# Analog_Voltmeter.net
KiCad netlist of a schematic drawn in Altium Designer
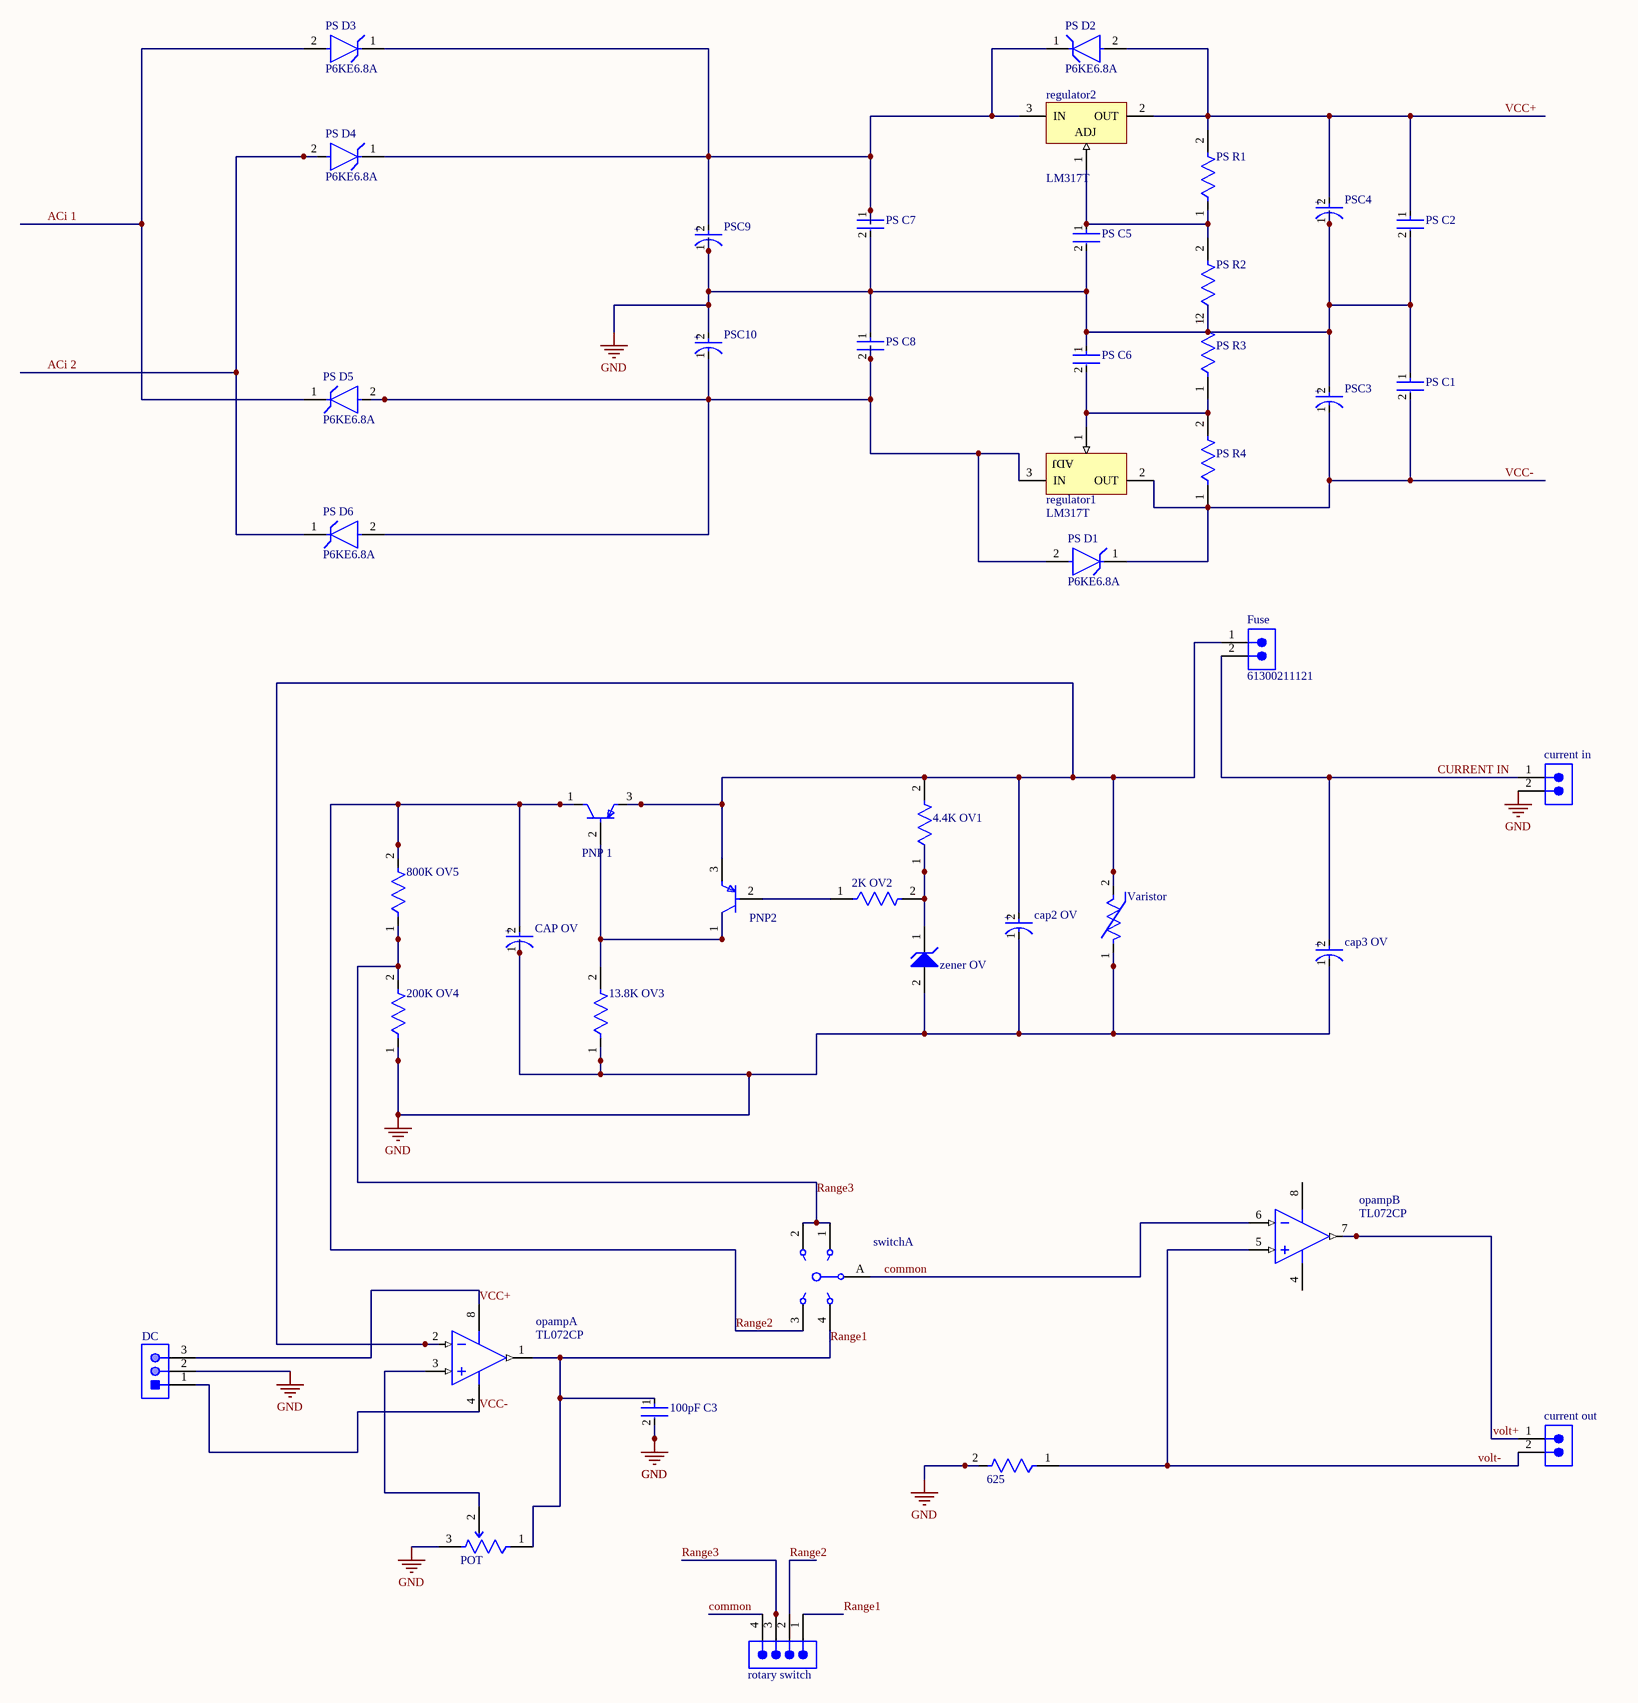
[diagram p0: Analog Voltmeter.SchDoc]

(export (version "E")
  (design (tool "Eeschema 10.0.6"))
  (components
    (comp (ref "2K OV2")
      (value "MRS25000C1002FCT00")
      (footprint "FP-MRS25-MFG")
      (fields (field (name "TOLERANCE") "1%"))
      (libsource (lib "Altium Content Vault") (part "1029c3af85768c4190bb7ad29bc67b5"))
    )
    (comp (ref "4.4K OV1")
      (value "MRS25000C1002FCT00")
      (footprint "FP-MRS25-MFG")
      (fields (field (name "TOLERANCE") "1%"))
      (libsource (lib "Altium Content Vault") (part "1029c3af85768c4190bb7ad29bc67b5"))
    )
    (comp (ref "13.8K OV3")
      (value "MRS25000C1002FCT00")
      (footprint "FP-MRS25-MFG")
      (fields (field (name "TOLERANCE") "1%"))
      (libsource (lib "Altium Content Vault") (part "1029c3af85768c4190bb7ad29bc67b5"))
    )
    (comp (ref "100pF C3")
      (value "K104K15X7RF5TH5")
      (footprint "FP-K15H5-MFG")
      (description "CAP CER 0.1UF 50V X7R RADIAL")
      (fields (field (name "TOLERANCE") "10%") (field (name "VOLTAGE") "50V"))
      (libsource (lib "Altium Content Vault") (part "02cd4be3c70576c341d710602a673aa"))
    )
    (comp (ref "200K OV4")
      (value "MRS25000C1002FCT00")
      (footprint "FP-MRS25-MFG")
      (fields (field (name "TOLERANCE") "1%"))
      (libsource (lib "Altium Content Vault") (part "1029c3af85768c4190bb7ad29bc67b5"))
    )
    (comp (ref "625")
      (value "MRS25000C1002FCT00")
      (footprint "FP-MRS25-MFG")
      (fields (field (name "TOLERANCE") "1%"))
      (libsource (lib "Altium Content Vault") (part "1029c3af85768c4190bb7ad29bc67b5"))
    )
    (comp (ref "800K OV5")
      (value "MRS25000C1002FCT00")
      (footprint "FP-MRS25-MFG")
      (fields (field (name "TOLERANCE") "1%"))
      (libsource (lib "Altium Content Vault") (part "1029c3af85768c4190bb7ad29bc67b5"))
    )
    (comp (ref "CAP OV")
      (value "ESL107M050AGMAA")
      (footprint "FP-ESLGM-MFG")
      (description "CAP ALUM 100UF 20% 50V THRU HOLE")
      (fields
        (field (name "TOLERANCE") "20%")
        (field (name "OCTOPART") "https://octopart.com/esl107m050agmaa-kemet-84758890")
      )
      (libsource (lib "Altium Content Vault") (part "a00bbbee19879c290e62620ae7e47b1"))
    )
    (comp (ref "cap2 OV")
      (value "ESL107M050AGMAA")
      (footprint "FP-ESLGM-MFG")
      (description "CAP ALUM 100UF 20% 50V THRU HOLE")
      (fields
        (field (name "TOLERANCE") "20%")
        (field (name "OCTOPART") "https://octopart.com/esl107m050agmaa-kemet-84758890")
      )
      (libsource (lib "Altium Content Vault") (part "a00bbbee19879c290e62620ae7e47b1"))
    )
    (comp (ref "cap3 OV")
      (value "ESL107M050AGMAA")
      (footprint "FP-ESLGM-MFG")
      (description "CAP ALUM 100UF 20% 50V THRU HOLE")
      (fields
        (field (name "TOLERANCE") "20%")
        (field (name "OCTOPART") "https://octopart.com/esl107m050agmaa-kemet-84758890")
      )
      (libsource (lib "Altium Content Vault") (part "a00bbbee19879c290e62620ae7e47b1"))
    )
    (comp (ref "current in")
      (value "61300211121")
      (footprint "61300211121")
      (libsource (lib "Altium Content Vault") (part "Header_Male_1R_02P"))
    )
    (comp (ref "current out")
      (value "61300211121")
      (footprint "61300211121")
      (libsource (lib "Altium Content Vault") (part "Header_Male_1R_02P"))
    )
    (comp (ref "DC")
      (value "22-28-4033")
      (footprint "MOLX-22-28-4033_V")
      (description "Male Header, Pitch 2.54 mm, 1 x 3 Position, Height 8.38 mm, Tail Length 3.18 mm, RoHS, Bulk")
      (fields (field (name "MANUFACTURER") "Molex"))
      (libsource (lib "Altium Content Vault") (part "CN-1P-M-R3"))
    )
    (comp (ref "Fuse")
      (value "61300211121")
      (footprint "61300211121")
      (libsource (lib "Altium Content Vault") (part "Header_Male_1R_02P"))
    )
    (comp (ref "opamp")
      (value "TL072CP")
      (footprint "P0008A")
      (fields (field (name "MANUFACTURER") "Texas Instruments"))
      (libsource (lib "Altium Content Vault") (part "TI-AMP-D6-2-8_D"))
    )
    (comp (ref "PNP 1")
      (value "BC558BTA")
      (footprint "FP-135AR-MFG")
      (description "BC558BTA Small Signal Bipolar Transistor, 0.1A I(C), 30V V(BR)CEO, 1-Element, PNP, Silicon, TO-92")
      (libsource (lib "Altium Content Vault") (part "9e2844d3eb996af6824d2c99fe21afc"))
    )
    (comp (ref "PNP2")
      (value "BC558BTA")
      (footprint "FP-135AR-MFG")
      (description "BC558BTA Small Signal Bipolar Transistor, 0.1A I(C), 30V V(BR)CEO, 1-Element, PNP, Silicon, TO-92")
      (libsource (lib "Altium Content Vault") (part "9e2844d3eb996af6824d2c99fe21afc"))
    )
    (comp (ref "POT")
      (value "3362P-1-503TLF")
      (footprint "FP-3362P-1-503TLF-MFG")
      (description "TRIMMER 50K OHM 0.5W PC PIN TOP")
      (fields (field (name "TOLERANCE") "10%"))
      (libsource (lib "Altium Content Vault") (part "2dcfd2547301a7d3209a5e99acfd772"))
    )
    (comp (ref "PS C1")
      (value "K104K15X7RF5TH5")
      (footprint "FP-K15H5-MFG")
      (description "CAP CER 0.1UF 50V X7R RADIAL")
      (fields (field (name "TOLERANCE") "10%") (field (name "VOLTAGE") "50V"))
      (libsource (lib "Altium Content Vault") (part "02cd4be3c70576c341d710602a673aa"))
    )
    (comp (ref "PS C2")
      (value "K104K15X7RF5TH5")
      (footprint "FP-K15H5-MFG")
      (description "CAP CER 0.1UF 50V X7R RADIAL")
      (fields (field (name "TOLERANCE") "10%") (field (name "VOLTAGE") "50V"))
      (libsource (lib "Altium Content Vault") (part "02cd4be3c70576c341d710602a673aa"))
    )
    (comp (ref "PS C5")
      (value "K104K15X7RF5TH5")
      (footprint "FP-K15H5-MFG")
      (description "CAP CER 0.1UF 50V X7R RADIAL")
      (fields (field (name "TOLERANCE") "10%") (field (name "VOLTAGE") "50V"))
      (libsource (lib "Altium Content Vault") (part "02cd4be3c70576c341d710602a673aa"))
    )
    (comp (ref "PS C6")
      (value "K104K15X7RF5TH5")
      (footprint "FP-K15H5-MFG")
      (description "CAP CER 0.1UF 50V X7R RADIAL")
      (fields (field (name "TOLERANCE") "10%") (field (name "VOLTAGE") "50V"))
      (libsource (lib "Altium Content Vault") (part "02cd4be3c70576c341d710602a673aa"))
    )
    (comp (ref "PS C7")
      (value "K104K15X7RF5TH5")
      (footprint "FP-K15H5-MFG")
      (description "CAP CER 0.1UF 50V X7R RADIAL")
      (fields (field (name "TOLERANCE") "10%") (field (name "VOLTAGE") "50V"))
      (libsource (lib "Altium Content Vault") (part "02cd4be3c70576c341d710602a673aa"))
    )
    (comp (ref "PS C8")
      (value "K104K15X7RF5TH5")
      (footprint "FP-K15H5-MFG")
      (description "CAP CER 0.1UF 50V X7R RADIAL")
      (fields (field (name "TOLERANCE") "10%") (field (name "VOLTAGE") "50V"))
      (libsource (lib "Altium Content Vault") (part "02cd4be3c70576c341d710602a673aa"))
    )
    (comp (ref "PS D1")
      (value "P6KE6.8A")
      (footprint "FP-P6KE-MFG")
      (description "TVS DIODE 5.8V 10.5V DO204AC")
      (fields
        (field (name "MANUFACTURER") "Littelfuse Inc")
        (field (name "OCTOPART") "https://octopart.com/p6ke6.8a-littelfuse-20808")
      )
      (libsource (lib "Altium Content Vault") (part "f813f71cba58e380607f5dd3caf9714"))
    )
    (comp (ref "PS D2")
      (value "P6KE6.8A")
      (footprint "FP-P6KE-MFG")
      (description "TVS DIODE 5.8V 10.5V DO204AC")
      (fields
        (field (name "MANUFACTURER") "Littelfuse Inc")
        (field (name "OCTOPART") "https://octopart.com/p6ke6.8a-littelfuse-20808")
      )
      (libsource (lib "Altium Content Vault") (part "f813f71cba58e380607f5dd3caf9714"))
    )
    (comp (ref "PS D3")
      (value "P6KE6.8A")
      (footprint "FP-P6KE-MFG")
      (description "TVS DIODE 5.8V 10.5V DO204AC")
      (fields
        (field (name "MANUFACTURER") "Littelfuse Inc")
        (field (name "OCTOPART") "https://octopart.com/p6ke6.8a-littelfuse-20808")
      )
      (libsource (lib "Altium Content Vault") (part "f813f71cba58e380607f5dd3caf9714"))
    )
    (comp (ref "PS D4")
      (value "P6KE6.8A")
      (footprint "FP-P6KE-MFG")
      (description "TVS DIODE 5.8V 10.5V DO204AC")
      (fields
        (field (name "MANUFACTURER") "Littelfuse Inc")
        (field (name "OCTOPART") "https://octopart.com/p6ke6.8a-littelfuse-20808")
      )
      (libsource (lib "Altium Content Vault") (part "f813f71cba58e380607f5dd3caf9714"))
    )
    (comp (ref "PS D5")
      (value "P6KE6.8A")
      (footprint "FP-P6KE-MFG")
      (description "TVS DIODE 5.8V 10.5V DO204AC")
      (fields
        (field (name "MANUFACTURER") "Littelfuse Inc")
        (field (name "OCTOPART") "https://octopart.com/p6ke6.8a-littelfuse-20808")
      )
      (libsource (lib "Altium Content Vault") (part "f813f71cba58e380607f5dd3caf9714"))
    )
    (comp (ref "PS D6")
      (value "P6KE6.8A")
      (footprint "FP-P6KE-MFG")
      (description "TVS DIODE 5.8V 10.5V DO204AC")
      (fields
        (field (name "MANUFACTURER") "Littelfuse Inc")
        (field (name "OCTOPART") "https://octopart.com/p6ke6.8a-littelfuse-20808")
      )
      (libsource (lib "Altium Content Vault") (part "f813f71cba58e380607f5dd3caf9714"))
    )
    (comp (ref "PS R1")
      (value "MRS25000C1002FCT00")
      (footprint "FP-MRS25-MFG")
      (fields (field (name "TOLERANCE") "1%"))
      (libsource (lib "Altium Content Vault") (part "1029c3af85768c4190bb7ad29bc67b5"))
    )
    (comp (ref "PS R2")
      (value "MRS25000C1002FCT00")
      (footprint "FP-MRS25-MFG")
      (fields (field (name "TOLERANCE") "1%"))
      (libsource (lib "Altium Content Vault") (part "1029c3af85768c4190bb7ad29bc67b5"))
    )
    (comp (ref "PS R3")
      (value "MRS25000C1002FCT00")
      (footprint "FP-MRS25-MFG")
      (fields (field (name "TOLERANCE") "1%"))
      (libsource (lib "Altium Content Vault") (part "1029c3af85768c4190bb7ad29bc67b5"))
    )
    (comp (ref "PS R4")
      (value "MRS25000C1002FCT00")
      (footprint "FP-MRS25-MFG")
      (fields (field (name "TOLERANCE") "1%"))
      (libsource (lib "Altium Content Vault") (part "1029c3af85768c4190bb7ad29bc67b5"))
    )
    (comp (ref "PSC3")
      (value "ESL107M050AGMAA")
      (footprint "FP-ESLGM-MFG")
      (description "CAP ALUM 100UF 20% 50V THRU HOLE")
      (fields
        (field (name "TOLERANCE") "20%")
        (field (name "OCTOPART") "https://octopart.com/esl107m050agmaa-kemet-84758890")
      )
      (libsource (lib "Altium Content Vault") (part "a00bbbee19879c290e62620ae7e47b1"))
    )
    (comp (ref "PSC4")
      (value "ESL107M050AGMAA")
      (footprint "FP-ESLGM-MFG")
      (description "CAP ALUM 100UF 20% 50V THRU HOLE")
      (fields
        (field (name "TOLERANCE") "20%")
        (field (name "OCTOPART") "https://octopart.com/esl107m050agmaa-kemet-84758890")
      )
      (libsource (lib "Altium Content Vault") (part "a00bbbee19879c290e62620ae7e47b1"))
    )
    (comp (ref "PSC9")
      (value "ESL107M050AGMAA")
      (footprint "FP-ESLGM-MFG")
      (description "CAP ALUM 100UF 20% 50V THRU HOLE")
      (fields
        (field (name "TOLERANCE") "20%")
        (field (name "OCTOPART") "https://octopart.com/esl107m050agmaa-kemet-84758890")
      )
      (libsource (lib "Altium Content Vault") (part "a00bbbee19879c290e62620ae7e47b1"))
    )
    (comp (ref "PSC10")
      (value "ESL107M050AGMAA")
      (footprint "FP-ESLGM-MFG")
      (description "CAP ALUM 100UF 20% 50V THRU HOLE")
      (fields
        (field (name "TOLERANCE") "20%")
        (field (name "OCTOPART") "https://octopart.com/esl107m050agmaa-kemet-84758890")
      )
      (libsource (lib "Altium Content Vault") (part "a00bbbee19879c290e62620ae7e47b1"))
    )
    (comp (ref "regulator1")
      (value "LM317T")
      (footprint "TO-220")
      (description "1.5A, 1.2V to 37V Adjustable Voltage Regulator, 3-Pin TO-220")
      (libsource (lib "Altium Content Vault") (part "PM-REG-117-SIL3"))
    )
    (comp (ref "regulator2")
      (value "LM317T")
      (footprint "TO-220")
      (description "1.5A, 1.2V to 37V Adjustable Voltage Regulator, 3-Pin TO-220")
      (libsource (lib "") (part "PM-REG-117-SIL3_1"))
    )
    (comp (ref "rotary switch")
      (value "61300411121")
      (footprint "61300411121")
      (libsource (lib "Altium Content Vault") (part "Header_Male_1R_04P"))
    )
    (comp (ref "switch")
      (value "A30415RNCQ")
      (footprint "CKCP-A30415RNCQ-15_V")
      (description "A Series Rotary Switch, 3 Poles, 4 Positions, 30 deg Angle of Throw, -30 to 85 degC, RoHS")
      (fields (field (name "MANUFACTURER") "C&K Components"))
      (libsource (lib "Altium Content Vault") (part "CKCP-SW_3P4T-15"))
    )
    (comp (ref "Varistor")
      (value "MOV-10D201KTR")
      (footprint "FP-MOV-10D201KTR-MFG")
      (description "VARISTOR 200V 2.5KA DISC 10MM")
      (fields
        (field (name "MANUFACTURER") "Bourns Inc.")
        (field (name "OCTOPART") "https://octopart.com/mov-10d201ktr-bourns-19184757")
      )
      (libsource (lib "Altium Content Vault") (part "78a88060d5b7b043d6e48adc4284376"))
    )
    (comp (ref "zener OV")
      (value "1N5347BRLG")
      (footprint "ONSC-SURMETIC40-2-017AA-01")
      (description "5 W Zener Voltage Regulator, 2-Pin Surmetic(TM) 40, Pb-Free, Tape and Reel")
      (fields (field (name "MANUFACTURER") "On Semiconductor"))
      (libsource (lib "Altium Content Vault") (part "ONSC-K1A2-2"))
    )
  )
  (nets
    (net (code "2") (name "/ACi 1") (class "Default")
      (node (ref "PS D3") (pin "2") (pinfunction "A_2") (pintype "passive"))
      (node (ref "PS D5") (pin "1") (pinfunction "C_1") (pintype "passive"))
    )
    (net (code "3") (name "/ACi 2") (class "Default")
      (node (ref "PS D4") (pin "2") (pinfunction "A_2") (pintype "passive"))
      (node (ref "PS D6") (pin "1") (pinfunction "C_1") (pintype "passive"))
    )
    (net (code "4") (name "/CURRENT IN") (class "Default")
      (node (ref "Fuse") (pin "2") (pinfunction "2_2") (pintype "passive"))
      (node (ref "cap3 OV") (pin "2") (pinfunction "A_2") (pintype "passive"))
      (node (ref "current in") (pin "1") (pinfunction "1_1") (pintype "passive"))
    )
    (net (code "5") (name "/Range1") (class "Default")
      (node (ref "100pF C3") (pin "1") (pinfunction "1_1") (pintype "passive"))
      (node (ref "POT") (pin "1") (pinfunction "CCW_1") (pintype "passive"))
      (node (ref "opamp") (pin "1") (pinfunction "OUT1_1") (pintype "output"))
      (node (ref "rotary switch") (pin "1") (pinfunction "1_1") (pintype "passive"))
      (node (ref "switch") (pin "4") (pinfunction "4_4") (pintype "passive"))
    )
    (net (code "6") (name "/Range2") (class "Default")
      (node (ref "800K OV5") (pin "2") (pinfunction "2_2") (pintype "passive"))
      (node (ref "CAP OV") (pin "2") (pinfunction "A_2") (pintype "passive"))
      (node (ref "PNP 1") (pin "1") (pinfunction "C_1") (pintype "passive"))
      (node (ref "rotary switch") (pin "2") (pinfunction "2_2") (pintype "passive"))
      (node (ref "switch") (pin "3") (pinfunction "3_3") (pintype "passive"))
    )
    (net (code "7") (name "/Range3") (class "Default")
      (node (ref "200K OV4") (pin "2") (pinfunction "2_2") (pintype "passive"))
      (node (ref "800K OV5") (pin "1") (pinfunction "1_1") (pintype "passive"))
      (node (ref "rotary switch") (pin "3") (pinfunction "3_3") (pintype "passive"))
      (node (ref "switch") (pin "1") (pinfunction "1_1") (pintype "passive"))
      (node (ref "switch") (pin "2") (pinfunction "2_2") (pintype "passive"))
    )
    (net (code "8") (name "/VCC+") (class "Default")
      (node (ref "DC") (pin "3") (pinfunction "3_3") (pintype "passive"))
      (node (ref "PS C2") (pin "1") (pinfunction "1_1") (pintype "passive"))
      (node (ref "PS D2") (pin "2") (pinfunction "A_2") (pintype "passive"))
      (node (ref "PS R1") (pin "2") (pinfunction "2_2") (pintype "passive"))
      (node (ref "PSC4") (pin "2") (pinfunction "A_2") (pintype "passive"))
      (node (ref "opamp") (pin "8") (pinfunction "VCC+_8") (pintype "power_in"))
      (node (ref "regulator2") (pin "2") (pinfunction "OUT_2") (pintype "power_in"))
    )
    (net (code "9") (name "/VCC-") (class "Default")
      (node (ref "DC") (pin "1") (pinfunction "1_1") (pintype "passive"))
      (node (ref "PS C1") (pin "2") (pinfunction "2_2") (pintype "passive"))
      (node (ref "PS D1") (pin "1") (pinfunction "C_1") (pintype "passive"))
      (node (ref "PS R4") (pin "1") (pinfunction "1_1") (pintype "passive"))
      (node (ref "PSC3") (pin "1") (pinfunction "C_1") (pintype "passive"))
      (node (ref "opamp") (pin "4") (pinfunction "VCC-_4") (pintype "power_in"))
      (node (ref "regulator1") (pin "2") (pinfunction "OUT_2") (pintype "power_in"))
    )
    (net (code "10") (name "/common") (class "Default")
      (node (ref "opamp") (pin "6") (pinfunction "IN2-_6") (pintype "input"))
      (node (ref "rotary switch") (pin "4") (pinfunction "4_4") (pintype "passive"))
      (node (ref "switch") (pin "A") (pinfunction "A_A") (pintype "passive"))
    )
    (net (code "11") (name "/volt+") (class "Default")
      (node (ref "current out") (pin "1") (pinfunction "1_1") (pintype "passive"))
      (node (ref "opamp") (pin "7") (pinfunction "OUT2_7") (pintype "output"))
    )
    (net (code "12") (name "/volt-") (class "Default")
      (node (ref "625") (pin "1") (pinfunction "1_1") (pintype "passive"))
      (node (ref "current out") (pin "2") (pinfunction "2_2") (pintype "passive"))
      (node (ref "opamp") (pin "5") (pinfunction "IN2+_5") (pintype "input"))
    )
    (net (code "13") (name "GND") (class "Default")
      (node (ref "100pF C3") (pin "2") (pinfunction "2_2") (pintype "passive"))
      (node (ref "13.8K OV3") (pin "1") (pinfunction "1_1") (pintype "passive"))
      (node (ref "200K OV4") (pin "1") (pinfunction "1_1") (pintype "passive"))
      (node (ref "625") (pin "2") (pinfunction "2_2") (pintype "passive"))
      (node (ref "CAP OV") (pin "1") (pinfunction "C_1") (pintype "passive"))
      (node (ref "DC") (pin "2") (pinfunction "2_2") (pintype "passive"))
      (node (ref "POT") (pin "3") (pinfunction "CW_3") (pintype "passive"))
      (node (ref "PS C1") (pin "1") (pinfunction "1_1") (pintype "passive"))
      (node (ref "PS C2") (pin "2") (pinfunction "2_2") (pintype "passive"))
      (node (ref "PS C5") (pin "2") (pinfunction "2_2") (pintype "passive"))
      (node (ref "PS C6") (pin "1") (pinfunction "1_1") (pintype "passive"))
      (node (ref "PS C7") (pin "2") (pinfunction "2_2") (pintype "passive"))
      (node (ref "PS C8") (pin "1") (pinfunction "1_1") (pintype "passive"))
      (node (ref "PS R2") (pin "1") (pinfunction "1_1") (pintype "passive"))
      (node (ref "PS R3") (pin "2") (pinfunction "2_2") (pintype "passive"))
      (node (ref "PSC10") (pin "2") (pinfunction "A_2") (pintype "passive"))
      (node (ref "PSC3") (pin "2") (pinfunction "A_2") (pintype "passive"))
      (node (ref "PSC4") (pin "1") (pinfunction "C_1") (pintype "passive"))
      (node (ref "PSC9") (pin "1") (pinfunction "C_1") (pintype "passive"))
      (node (ref "Varistor") (pin "1") (pinfunction "1_1") (pintype "passive"))
      (node (ref "cap2 OV") (pin "1") (pinfunction "C_1") (pintype "passive"))
      (node (ref "cap3 OV") (pin "1") (pinfunction "C_1") (pintype "passive"))
      (node (ref "current in") (pin "2") (pinfunction "2_2") (pintype "passive"))
      (node (ref "zener OV") (pin "2") (pinfunction "A_2") (pintype "passive"))
    )
    (net (code "14") (name "Net-(PNP 1-B)") (class "Default")
      (node (ref "13.8K OV3") (pin "2") (pinfunction "2_2") (pintype "passive"))
      (node (ref "PNP 1") (pin "2") (pinfunction "B_2") (pintype "passive"))
      (node (ref "PNP2") (pin "1") (pinfunction "C_1") (pintype "passive"))
    )
    (net (code "15") (name "Net-(PNP 1-E)") (class "Default")
      (node (ref "4.4K OV1") (pin "2") (pinfunction "2_2") (pintype "passive"))
      (node (ref "Fuse") (pin "1") (pinfunction "1_1") (pintype "passive"))
      (node (ref "PNP 1") (pin "3") (pinfunction "E_3") (pintype "passive"))
      (node (ref "PNP2") (pin "3") (pinfunction "E_3") (pintype "passive"))
      (node (ref "Varistor") (pin "2") (pinfunction "2_2") (pintype "passive"))
      (node (ref "cap2 OV") (pin "2") (pinfunction "A_2") (pintype "passive"))
      (node (ref "opamp") (pin "2") (pinfunction "IN1-_2") (pintype "input"))
    )
    (net (code "16") (name "Net-(PNP2-B)") (class "Default")
      (node (ref "2K OV2") (pin "1") (pinfunction "1_1") (pintype "passive"))
      (node (ref "PNP2") (pin "2") (pinfunction "B_2") (pintype "passive"))
    )
    (net (code "17") (name "Net-(POT-WIPER)") (class "Default")
      (node (ref "POT") (pin "2") (pinfunction "WIPER_2") (pintype "passive"))
      (node (ref "opamp") (pin "3") (pinfunction "IN1+_3") (pintype "input"))
    )
    (net (code "18") (name "Net-(PS D1-A)") (class "Default")
      (node (ref "PS C8") (pin "2") (pinfunction "2_2") (pintype "passive"))
      (node (ref "PS D1") (pin "2") (pinfunction "A_2") (pintype "passive"))
      (node (ref "PS D5") (pin "2") (pinfunction "A_2") (pintype "passive"))
      (node (ref "PS D6") (pin "2") (pinfunction "A_2") (pintype "passive"))
      (node (ref "PSC10") (pin "1") (pinfunction "C_1") (pintype "passive"))
      (node (ref "regulator1") (pin "3") (pinfunction "IN_3") (pintype "power_in"))
    )
    (net (code "19") (name "Net-(PS D2-C)") (class "Default")
      (node (ref "PS C7") (pin "1") (pinfunction "1_1") (pintype "passive"))
      (node (ref "PS D2") (pin "1") (pinfunction "C_1") (pintype "passive"))
      (node (ref "PS D3") (pin "1") (pinfunction "C_1") (pintype "passive"))
      (node (ref "PS D4") (pin "1") (pinfunction "C_1") (pintype "passive"))
      (node (ref "PSC9") (pin "2") (pinfunction "A_2") (pintype "passive"))
      (node (ref "regulator2") (pin "3") (pinfunction "IN_3") (pintype "power_in"))
    )
    (net (code "20") (name "Net-(regulator1-ADJ)") (class "Default")
      (node (ref "PS C6") (pin "2") (pinfunction "2_2") (pintype "passive"))
      (node (ref "PS R3") (pin "1") (pinfunction "1_1") (pintype "passive"))
      (node (ref "PS R4") (pin "2") (pinfunction "2_2") (pintype "passive"))
      (node (ref "regulator1") (pin "1") (pinfunction "ADJ_1") (pintype "input"))
    )
    (net (code "21") (name "Net-(regulator2-ADJ)") (class "Default")
      (node (ref "PS C5") (pin "1") (pinfunction "1_1") (pintype "passive"))
      (node (ref "PS R1") (pin "1") (pinfunction "1_1") (pintype "passive"))
      (node (ref "PS R2") (pin "2") (pinfunction "2_2") (pintype "passive"))
      (node (ref "regulator2") (pin "1") (pinfunction "ADJ_1") (pintype "input"))
    )
    (net (code "22") (name "Net-(zener OV-K)") (class "Default")
      (node (ref "2K OV2") (pin "2") (pinfunction "2_2") (pintype "passive"))
      (node (ref "4.4K OV1") (pin "1") (pinfunction "1_1") (pintype "passive"))
      (node (ref "zener OV") (pin "1") (pinfunction "K_1") (pintype "passive"))
    )
    (net (code "23") (name "unconnected-(opampB-VCC+-Pad8)") (class "Default")
      (node (ref "opamp") (pin "8") (pinfunction "VCC+_8") (pintype "power_in"))
    )
    (net (code "24") (name "unconnected-(opampB-VCC--Pad4)") (class "Default")
      (node (ref "opamp") (pin "4") (pinfunction "VCC-_4") (pintype "power_in"))
    )
  )
)
